# Car_Circuitry.net
KiCad netlist of a schematic drawn in Altium Designer
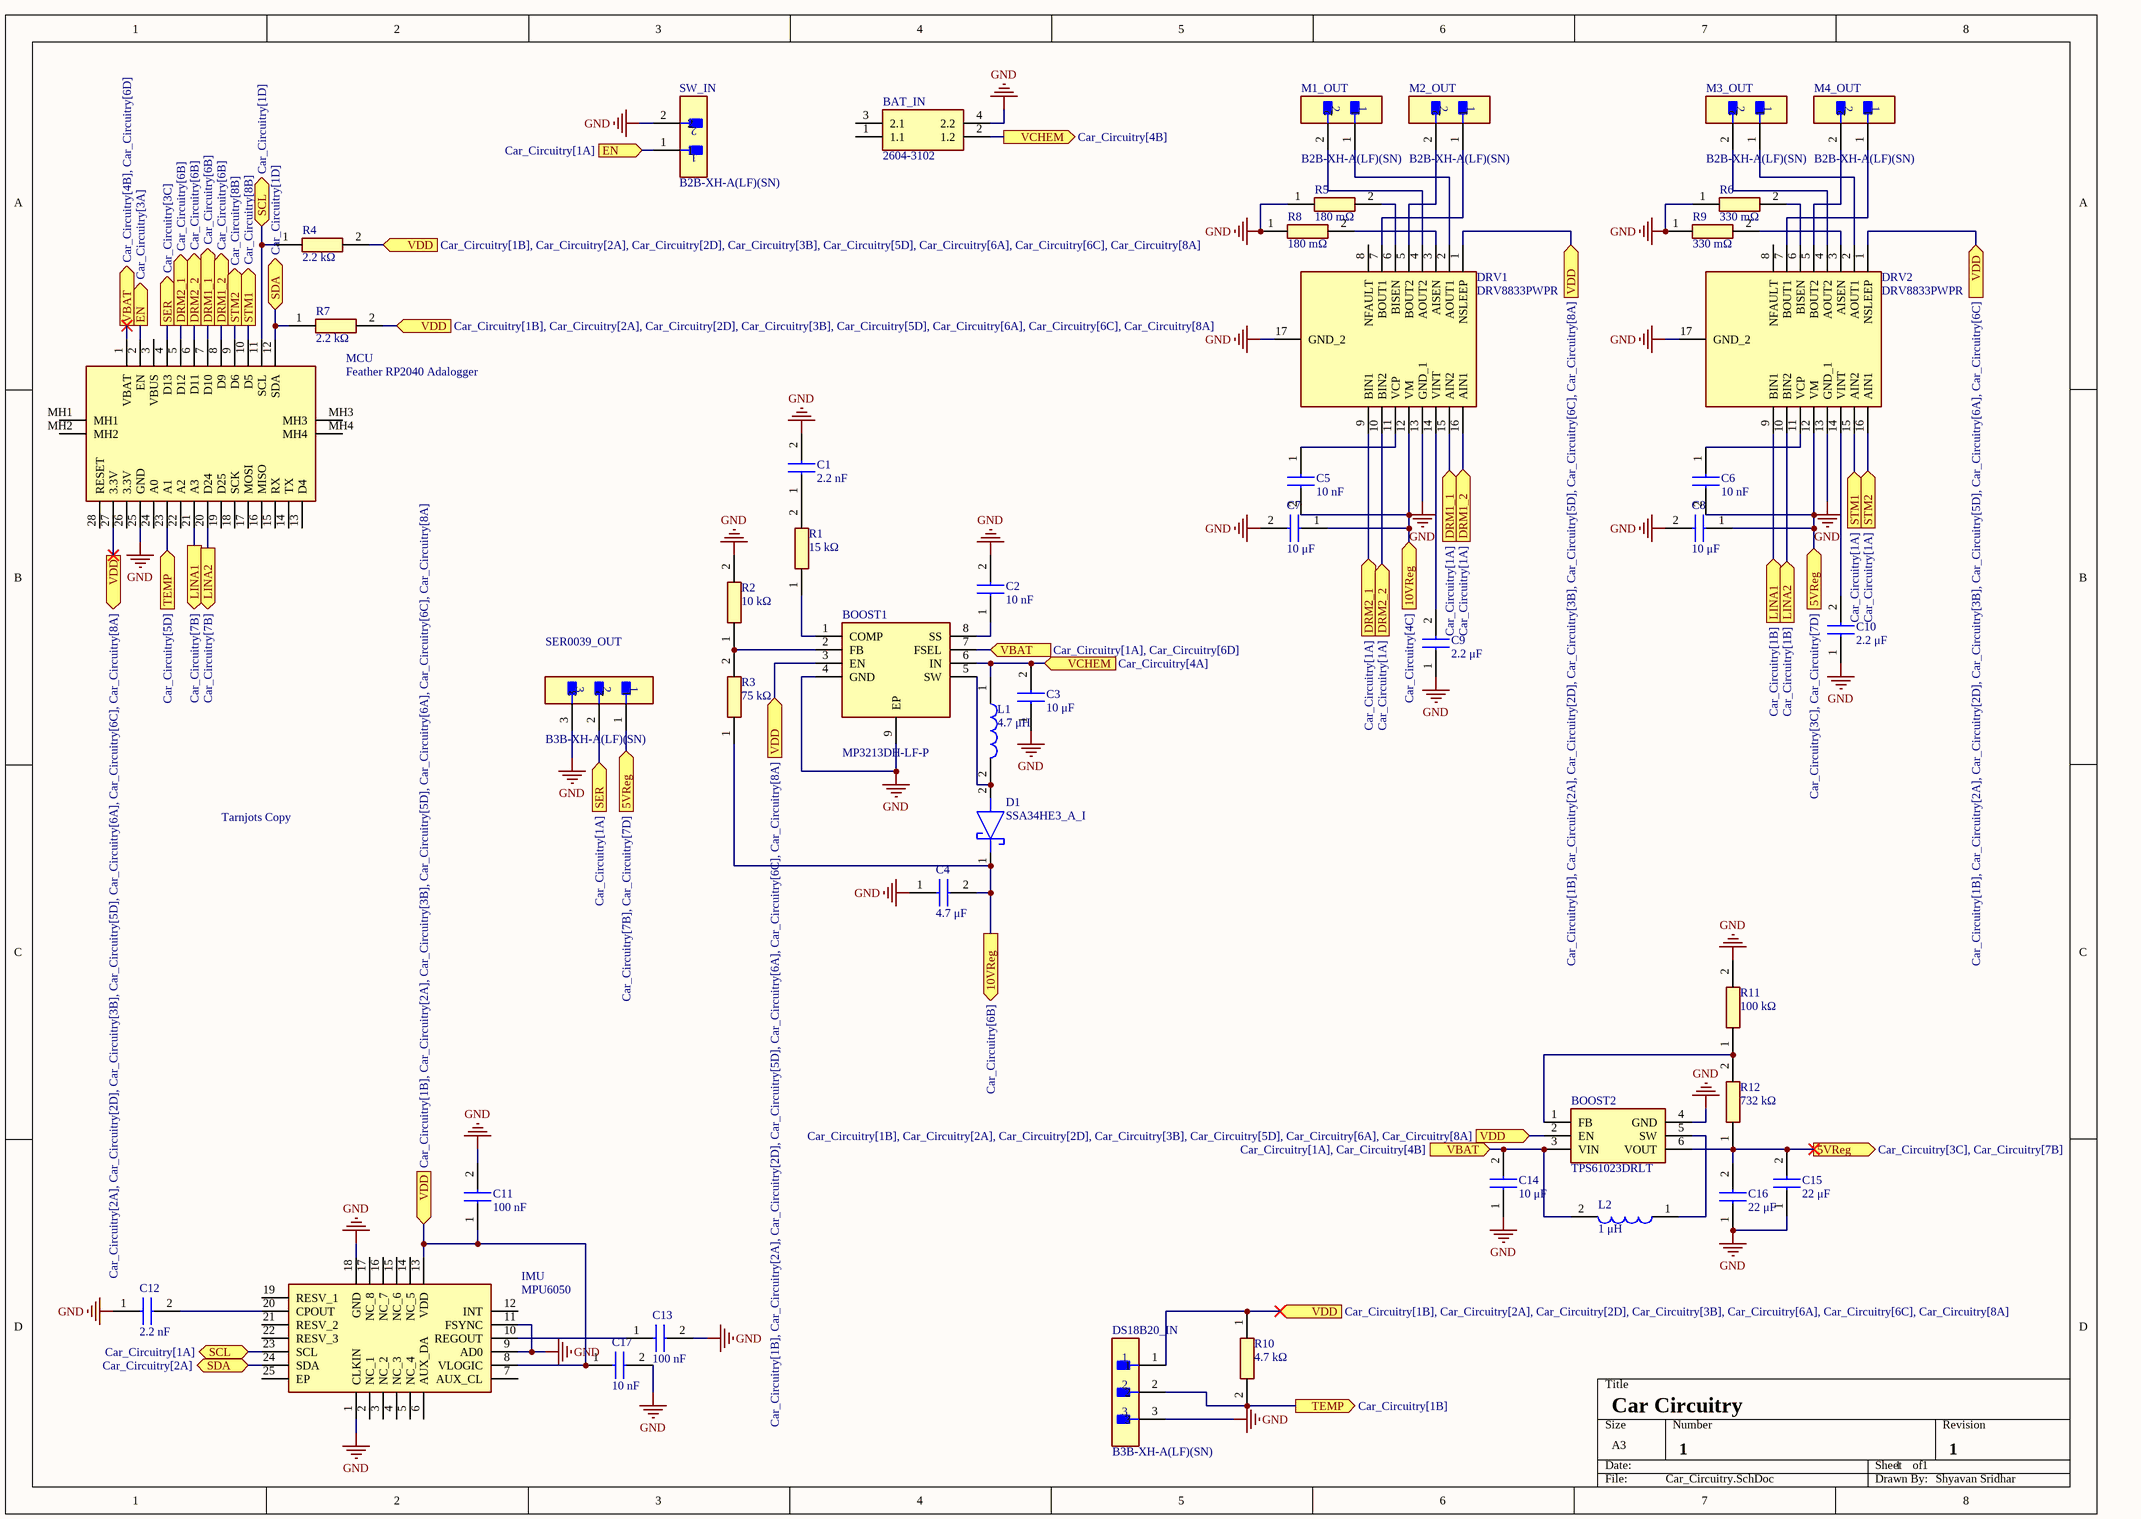
[diagram p0: Car_Circuitry.SchDoc]

(export (version "E")
  (design (tool "Eeschema 10.0.6"))
  (components
    (comp (ref "BAT_IN")
      (value "2604-3102")
      (footprint "SamacSys:26043102")
      (description "Connector")
      (libsource (lib "*") (part "2604-3102"))
    )
    (comp (ref "BOOST1")
      (value "MP3213DH-LF-P")
      (footprint "SamacSys:SOP65P490X110-9N")
      (description "Integrated Circuit")
      (fields (field (name "MOUSER PART NUMBER") "946-MP3213DHLFP"))
      (libsource (lib "*") (part "MP3213DH-LF-P"))
    )
    (comp (ref "BOOST2")
      (value "TPS61023DRLT")
      (footprint "SamacSys:SOTFL50P160X60-6N")
      (description "Integrated Circuit")
      (fields (field (name "MOUSER PART NUMBER") "595-TPS61023DRLT"))
      (libsource (lib "*") (part "TPS61023DRLT"))
    )
    (comp (ref "C1")
      (value "2.2 nF")
      (footprint "SamacSys:CAPC2012X75N")
      (description "Capacitor")
      (fields (field (name "MANUFACTURER_PART_NUMBER") "CL21B222KBANNNC"))
      (libsource (lib "*") (part "CL21B222KBANNNC"))
    )
    (comp (ref "C2")
      (value "10 nF")
      (footprint "SamacSys:CAPC2012X75N")
      (description "Capacitor")
      (fields
        (field (name "MANUFACTURER_PART_NUMBER") "CL21B103KBANNNC")
        (field (name "MOUSER PART NUMBER") "187-CL21B103KBANNNC")
      )
      (libsource (lib "*") (part "CL21B103KBANNNC"))
    )
    (comp (ref "C3")
      (value "10 μF")
      (footprint "SamacSys:CAPC2012X140N")
      (description "Capacitor")
      (fields
        (field (name "MANUFACTURER_PART_NUMBER") "CL21B106KOQNNNE")
        (field (name "MOUSER PART NUMBER") "187-CL21B106KOQNNNE")
      )
      (libsource (lib "*") (part "CL21B106KOQNNNE"))
    )
    (comp (ref "C4")
      (value "4.7 μF")
      (footprint "SamacSys:CAPC2012X135N")
      (description "Capacitor")
      (fields
        (field (name "MANUFACTURER_PART_NUMBER") "CL21B475KOFNNNE")
        (field (name "MOUSER PART NUMBER") "187-CL21B475KOFNNNE")
      )
      (libsource (lib "*") (part "CL21B475KOFNNNE"))
    )
    (comp (ref "C5")
      (value "10 nF")
      (footprint "SamacSys:CAPC2012X75N")
      (description "Capacitor")
      (fields
        (field (name "MANUFACTURER_PART_NUMBER") "CL21B103KBANNNC")
        (field (name "MOUSER PART NUMBER") "187-CL21B103KBANNNC")
      )
      (libsource (lib "*") (part "CL21B103KBANNNC"))
    )
    (comp (ref "C6")
      (value "10 nF")
      (footprint "SamacSys:CAPC2012X75N")
      (description "Capacitor")
      (fields
        (field (name "MANUFACTURER_PART_NUMBER") "CL21B103KBANNNC")
        (field (name "MOUSER PART NUMBER") "187-CL21B103KBANNNC")
      )
      (libsource (lib "*") (part "CL21B103KBANNNC"))
    )
    (comp (ref "C7")
      (value "10 μF")
      (footprint "SamacSys:CAPC2012X140N")
      (description "Capacitor")
      (fields
        (field (name "MANUFACTURER_PART_NUMBER") "CL21B106KOQNNNE")
        (field (name "MOUSER PART NUMBER") "187-CL21B106KOQNNNE")
      )
      (libsource (lib "*") (part "CL21B106KOQNNNE"))
    )
    (comp (ref "C8")
      (value "10 μF")
      (footprint "SamacSys:CAPC2012X140N")
      (description "Capacitor")
      (fields
        (field (name "MANUFACTURER_PART_NUMBER") "CL21B106KOQNNNE")
        (field (name "MOUSER PART NUMBER") "187-CL21B106KOQNNNE")
      )
      (libsource (lib "*") (part "CL21B106KOQNNNE"))
    )
    (comp (ref "C9")
      (value "2.2 μF")
      (footprint "SamacSys:CAPC2012X135N")
      (description "Capacitor")
      (fields (field (name "MANUFACTURER_PART_NUMBER") "CL21B225KAFNNWE"))
      (libsource (lib "*") (part "CL21B225KAFNNWE"))
    )
    (comp (ref "C10")
      (value "2.2 μF")
      (footprint "SamacSys:CAPC2012X135N")
      (description "Capacitor")
      (fields (field (name "MANUFACTURER_PART_NUMBER") "CL21B225KAFNNWE"))
      (libsource (lib "*") (part "CL21B225KAFNNWE"))
    )
    (comp (ref "C11")
      (value "100 nF")
      (footprint "SamacSys:CAPC2012X95N")
      (description "Capacitor")
      (fields
        (field (name "MANUFACTURER_PART_NUMBER") "CL21B104KBCNNNC")
        (field (name "MOUSER PART NUMBER") "187-CL21B104KBCNNNC")
      )
      (libsource (lib "*") (part "CL21B104KBCNNNC"))
    )
    (comp (ref "C12")
      (value "2.2 nF")
      (footprint "SamacSys:CAPC2012X75N")
      (description "Capacitor")
      (fields (field (name "MANUFACTURER_PART_NUMBER") "CL21B222KBANNNC"))
      (libsource (lib "*") (part "CL21B222KBANNNC"))
    )
    (comp (ref "C13")
      (value "100 nF")
      (footprint "SamacSys:CAPC2012X95N")
      (description "Capacitor")
      (fields
        (field (name "MANUFACTURER_PART_NUMBER") "CL21B104KBCNNNC")
        (field (name "MOUSER PART NUMBER") "187-CL21B104KBCNNNC")
      )
      (libsource (lib "*") (part "CL21B104KBCNNNC"))
    )
    (comp (ref "C14")
      (value "10 μF")
      (footprint "SamacSys:CAPC2012X140N")
      (description "Capacitor")
      (fields
        (field (name "MANUFACTURER_PART_NUMBER") "CL21B106KOQNNNE")
        (field (name "MOUSER PART NUMBER") "187-CL21B106KOQNNNE")
      )
      (libsource (lib "*") (part "CL21B106KOQNNNE"))
    )
    (comp (ref "C15")
      (value "22 μF")
      (footprint "SamacSys:CAPC3216X180N")
      (description "Capacitor")
      (fields
        (field (name "MANUFACTURER_PART_NUMBER") "CL31B226KPHNNNE")
        (field (name "MOUSER PART NUMBER") "187-CL31B226KPHNNNE")
      )
      (libsource (lib "*") (part "CL31B226KPHNNNE"))
    )
    (comp (ref "C16")
      (value "22 μF")
      (footprint "SamacSys:CAPC3216X180N")
      (description "Capacitor")
      (fields
        (field (name "MANUFACTURER_PART_NUMBER") "CL31B226KPHNNNE")
        (field (name "MOUSER PART NUMBER") "187-CL31B226KPHNNNE")
      )
      (libsource (lib "*") (part "CL31B226KPHNNNE"))
    )
    (comp (ref "C17")
      (value "10 nF")
      (footprint "SamacSys:CAPC2012X75N")
      (description "Capacitor")
      (fields
        (field (name "MANUFACTURER_PART_NUMBER") "CL21B103KBANNNC")
        (field (name "MOUSER PART NUMBER") "187-CL21B103KBANNNC")
      )
      (libsource (lib "*") (part "CL21B103KBANNNC"))
    )
    (comp (ref "D1")
      (value "SSA34HE3_A_I")
      (footprint "SamacSys:DIONM5127X229N")
      (description "Schottky Diode")
      (fields
        (field (name "MANUFACTURER_PART_NUMBER") "SSA34HE3_A/I")
        (field (name "MOUSER PART NUMBER") "78-SSA34HE3_A/I")
      )
      (libsource (lib "*") (part "SSA34HE3_A_I"))
    )
    (comp (ref "DRV1")
      (value "DRV8833PWPR")
      (footprint "SamacSys:SOP65P640X120-17N")
      (description "Integrated Circuit")
      (fields
        (field (name "MANUFACTURER_PART_NUMBER") "DRV8833PWP")
        (field (name "MOUSER PART NUMBER") "595-DRV8833PWP")
      )
      (libsource (lib "*") (part "DRV8833PWP"))
    )
    (comp (ref "DRV2")
      (value "DRV8833PWPR")
      (footprint "SamacSys:SOP65P640X120-17N")
      (description "Integrated Circuit")
      (fields
        (field (name "MANUFACTURER_PART_NUMBER") "DRV8833PWP")
        (field (name "MOUSER PART NUMBER") "595-DRV8833PWP")
      )
      (libsource (lib "*") (part "DRV8833PWP"))
    )
    (comp (ref "DS18B20_IN")
      (value "B3B-XH-A(LF)(SN)")
      (footprint "FP-B3B-XH-A_LF_SN-MFG")
      (description "CONN HEADER VERT 3POS 2.5MM")
      (libsource (lib "") (part "0d3f023dd272f625e17a2be33dea85f_1"))
    )
    (comp (ref "IMU")
      (value "MPU6050")
      (footprint "SamacSys:MPU6050")
      (description "IMU")
      (libsource (lib "*") (part "MPU6050"))
    )
    (comp (ref "L1")
      (value "4.7 μH")
      (footprint "SamacSys:CDRH8D43NP4R7NC")
      (description "Inductor")
      (fields
        (field (name "MANUFACTURER_PART_NUMBER") "CDRH8D43NP-4R7NC")
        (field (name "MOUSER PART NUMBER") "851-CDRH8D43NP-4R7NC")
      )
      (libsource (lib "*") (part "CDRH8D43NP-4R7NC"))
    )
    (comp (ref "L2")
      (value "1 μH")
      (footprint "SamacSys:74438357010")
      (description "Inductor")
      (fields
        (field (name "MANUFACTURER_PART_NUMBER") "74438357010")
        (field (name "MOUSER PART NUMBER") "710-74438357010")
      )
      (libsource (lib "*") (part "74438357010"))
    )
    (comp (ref "M1_OUT")
      (value "B2B-XH-A(LF)(SN)")
      (footprint "FP-B2B-XH-A_LF_SN-MFG")
      (description "CONN HEADER VERT 2POS 2.5MM")
      (libsource (lib "Altium Content Vault") (part "3bc925449376181038e59eaffc5286c"))
    )
    (comp (ref "M2_OUT")
      (value "B2B-XH-A(LF)(SN)")
      (footprint "FP-B2B-XH-A_LF_SN-MFG")
      (description "CONN HEADER VERT 2POS 2.5MM")
      (libsource (lib "Altium Content Vault") (part "3bc925449376181038e59eaffc5286c"))
    )
    (comp (ref "M3_OUT")
      (value "B2B-XH-A(LF)(SN)")
      (footprint "FP-B2B-XH-A_LF_SN-MFG")
      (description "CONN HEADER VERT 2POS 2.5MM")
      (libsource (lib "Altium Content Vault") (part "3bc925449376181038e59eaffc5286c"))
    )
    (comp (ref "M4_OUT")
      (value "B2B-XH-A(LF)(SN)")
      (footprint "FP-B2B-XH-A_LF_SN-MFG")
      (description "CONN HEADER VERT 2POS 2.5MM")
      (libsource (lib "Altium Content Vault") (part "3bc925449376181038e59eaffc5286c"))
    )
    (comp (ref "MCU")
      (value "Feather RP2040 Adalogger")
      (footprint "SamacSys:2796")
      (description "Adafruit Microcontroller")
      (fields (field (name "MANUFACTURER_PART_NUMBER") "2796") (field (name "MOUSER PART NUMBER") "485-2796"))
      (libsource (lib "*") (part "2796"))
    )
    (comp (ref "R1")
      (value "15 kΩ")
      (footprint "SamacSys:RESC3216X70N")
      (description "Resistor")
      (fields (field (name "MANUFACTURER_PART_NUMBER") "RMCF1206FT15K0"))
      (libsource (lib "*") (part "RMCF1206FT15K0"))
    )
    (comp (ref "R2")
      (value "10 kΩ")
      (footprint "SamacSys:RESC3216X70N")
      (description "Resistor")
      (fields
        (field (name "MANUFACTURER_PART_NUMBER") "RMCF1206FT10K0")
        (field (name "MOUSER PART NUMBER") "708-RMCF1206FT10K0")
      )
      (libsource (lib "*") (part "RMCF1206FT10K0"))
    )
    (comp (ref "R3")
      (value "75 kΩ")
      (footprint "SamacSys:RESC3116X65N")
      (description "Resistor")
      (fields
        (field (name "MANUFACTURER_PART_NUMBER") "RC1206FR-0775KL")
        (field (name "MOUSER PART NUMBER") "603-RC1206FR-0775KL")
      )
      (libsource (lib "*") (part "RC1206FR-0775KL"))
    )
    (comp (ref "R4")
      (value "2.2 kΩ")
      (footprint "SamacSys:RESAD1042W49L330D178")
      (description "Resistor")
      (fields (field (name "MANUFACTURER_PART_NUMBER") "RNMF14FTC2K20"))
      (libsource (lib "*") (part "RNMF14FTC2K20"))
    )
    (comp (ref "R5")
      (value "180 mΩ")
      (footprint "SamacSys:ERJ6_B_BW_R_LW_CW_D")
      (description "Resistor")
      (fields
        (field (name "MANUFACTURER_PART_NUMBER") "ERJ-6DSFR18V")
        (field (name "MOUSER PART NUMBER") "667-ERJ-6DSFR18V")
      )
      (libsource (lib "*") (part "ERJ-6DSFR18V"))
    )
    (comp (ref "R6")
      (value "330 mΩ")
      (footprint "SamacSys:ERJ6_B_BW_R_LW_CW_D")
      (description "Resistor")
      (fields
        (field (name "MANUFACTURER_PART_NUMBER") "ERJ-6DQFR33V")
        (field (name "MOUSER PART NUMBER") "667-ERJ-6DQFR33V")
      )
      (libsource (lib "*") (part "ERJ-6DQFR33V"))
    )
    (comp (ref "R7")
      (value "2.2 kΩ")
      (footprint "SamacSys:RESAD1042W49L330D178")
      (description "Resistor")
      (fields (field (name "MANUFACTURER_PART_NUMBER") "RNMF14FTC2K20"))
      (libsource (lib "*") (part "RNMF14FTC2K20"))
    )
    (comp (ref "R8")
      (value "180 mΩ")
      (footprint "SamacSys:ERJ6_B_BW_R_LW_CW_D")
      (description "Resistor")
      (fields
        (field (name "MANUFACTURER_PART_NUMBER") "ERJ-6DSFR18V")
        (field (name "MOUSER PART NUMBER") "667-ERJ-6DSFR18V")
      )
      (libsource (lib "*") (part "ERJ-6DSFR18V"))
    )
    (comp (ref "R9")
      (value "330 mΩ")
      (footprint "SamacSys:ERJ6_B_BW_R_LW_CW_D")
      (description "Resistor")
      (fields
        (field (name "MANUFACTURER_PART_NUMBER") "ERJ-6DQFR33V")
        (field (name "MOUSER PART NUMBER") "667-ERJ-6DQFR33V")
      )
      (libsource (lib "*") (part "ERJ-6DQFR33V"))
    )
    (comp (ref "R10")
      (value "4.7 kΩ")
      (footprint "SamacSys:RESAD1530W60L610D230")
      (description "Resistor")
      (fields
        (field (name "MANUFACTURER_PART_NUMBER") "CF1/4C472J")
        (field (name "MOUSER PART NUMBER") "660-CF1/4C472J")
      )
      (libsource (lib "*") (part "CF1_4C472J"))
    )
    (comp (ref "R11")
      (value "100 kΩ")
      (footprint "SamacSys:ERJ8ENF1000V")
      (description "Resistor")
      (fields
        (field (name "MANUFACTURER_PART_NUMBER") "ERJ-8ENF1003V")
        (field (name "MOUSER PART NUMBER") "667-ERJ-8ENF1003V")
      )
      (libsource (lib "*") (part "ERJ-8ENF1003V"))
    )
    (comp (ref "R12")
      (value "732 kΩ")
      (footprint "SamacSys:ERJ8ENF1000V")
      (description "Resistor")
      (fields
        (field (name "MANUFACTURER_PART_NUMBER") "ERJ-8ENF7323V")
        (field (name "MOUSER PART NUMBER") "667-ERJ-8ENF7323V")
      )
      (libsource (lib "*") (part "ERJ-8ENF7323V"))
    )
    (comp (ref "SER0039_OUT")
      (value "B3B-XH-A(LF)(SN)")
      (footprint "FP-B3B-XH-A_LF_SN-MFG")
      (description "CONN HEADER VERT 3POS 2.5MM")
      (libsource (lib "Altium Content Vault") (part "0d3f023dd272f625e17a2be33dea85f"))
    )
    (comp (ref "SW_IN")
      (value "B2B-XH-A(LF)(SN)")
      (footprint "FP-B2B-XH-A_LF_SN-MFG")
      (description "CONN HEADER VERT 2POS 2.5MM")
      (libsource (lib "") (part "3bc925449376181038e59eaffc5286c_1"))
    )
  )
  (nets
    (net (code "1") (name "/5VReg") (class "Default")
      (node (ref "BOOST2") (pin "6") (pinfunction "VOUT_6") (pintype "passive"))
      (node (ref "C15") (pin "2") (pinfunction "2_2") (pintype "passive"))
      (node (ref "C16") (pin "2") (pinfunction "2_2") (pintype "passive"))
      (node (ref "C6") (pin "2") (pinfunction "2_2") (pintype "passive"))
      (node (ref "C8") (pin "1") (pinfunction "1_1") (pintype "passive"))
      (node (ref "DRV2") (pin "12") (pinfunction "VM_12") (pintype "passive"))
      (node (ref "R12") (pin "1") (pinfunction "1_1") (pintype "passive"))
      (node (ref "SER0039_OUT") (pin "1") (pinfunction "1_1") (pintype "passive"))
    )
    (net (code "2") (name "/10VReg") (class "Default")
      (node (ref "C4") (pin "2") (pinfunction "2_2") (pintype "passive"))
      (node (ref "C5") (pin "2") (pinfunction "2_2") (pintype "passive"))
      (node (ref "C7") (pin "1") (pinfunction "1_1") (pintype "passive"))
      (node (ref "D1") (pin "1") (pinfunction "K_1") (pintype "passive"))
      (node (ref "DRV1") (pin "12") (pinfunction "VM_12") (pintype "passive"))
      (node (ref "R3") (pin "1") (pinfunction "1_1") (pintype "passive"))
    )
    (net (code "3") (name "/DRM1_1") (class "Default")
      (node (ref "DRV1") (pin "15") (pinfunction "AIN2_15") (pintype "passive"))
      (node (ref "MCU") (pin "7") (pinfunction "D10_7") (pintype "passive"))
    )
    (net (code "4") (name "/DRM1_2") (class "Default")
      (node (ref "DRV1") (pin "16") (pinfunction "AIN1_16") (pintype "passive"))
      (node (ref "MCU") (pin "8") (pinfunction "D9_8") (pintype "passive"))
    )
    (net (code "5") (name "/DRM2_1") (class "Default")
      (node (ref "DRV1") (pin "9") (pinfunction "BIN1_9") (pintype "passive"))
      (node (ref "MCU") (pin "5") (pinfunction "D12_5") (pintype "passive"))
    )
    (net (code "6") (name "/DRM2_2") (class "Default")
      (node (ref "DRV1") (pin "10") (pinfunction "BIN2_10") (pintype "passive"))
      (node (ref "MCU") (pin "6") (pinfunction "D11_6") (pintype "passive"))
    )
    (net (code "7") (name "/EN") (class "Default")
      (node (ref "MCU") (pin "2") (pinfunction "EN_2") (pintype "passive"))
      (node (ref "SW_IN") (pin "1") (pinfunction "1_1") (pintype "passive"))
    )
    (net (code "8") (name "/LINA1") (class "Default")
      (node (ref "DRV2") (pin "9") (pinfunction "BIN1_9") (pintype "passive"))
      (node (ref "MCU") (pin "21") (pinfunction "A3_21") (pintype "passive"))
    )
    (net (code "9") (name "/LINA2") (class "Default")
      (node (ref "DRV2") (pin "10") (pinfunction "BIN2_10") (pintype "passive"))
      (node (ref "MCU") (pin "20") (pinfunction "D24_20") (pintype "passive"))
    )
    (net (code "10") (name "/SCL") (class "Default")
      (node (ref "IMU") (pin "23") (pinfunction "SCL_23") (pintype "passive"))
      (node (ref "MCU") (pin "11") (pinfunction "SCL_11") (pintype "passive"))
      (node (ref "R4") (pin "1") (pinfunction "1_1") (pintype "passive"))
    )
    (net (code "11") (name "/SDA") (class "Default")
      (node (ref "IMU") (pin "24") (pinfunction "SDA_24") (pintype "passive"))
      (node (ref "MCU") (pin "12") (pinfunction "SDA_12") (pintype "passive"))
      (node (ref "R7") (pin "1") (pinfunction "1_1") (pintype "passive"))
    )
    (net (code "12") (name "/SER") (class "Default")
      (node (ref "MCU") (pin "4") (pinfunction "D13_4") (pintype "passive"))
      (node (ref "SER0039_OUT") (pin "2") (pinfunction "2_2") (pintype "passive"))
    )
    (net (code "13") (name "/STM1") (class "Default")
      (node (ref "DRV2") (pin "15") (pinfunction "AIN2_15") (pintype "passive"))
      (node (ref "MCU") (pin "10") (pinfunction "D5_10") (pintype "passive"))
    )
    (net (code "14") (name "/STM2") (class "Default")
      (node (ref "DRV2") (pin "16") (pinfunction "AIN1_16") (pintype "passive"))
      (node (ref "MCU") (pin "9") (pinfunction "D6_9") (pintype "passive"))
    )
    (net (code "15") (name "/TEMP") (class "Default")
      (node (ref "DS18B20_IN") (pin "2") (pinfunction "2_2") (pintype "passive"))
      (node (ref "MCU") (pin "23") (pinfunction "A1_23") (pintype "passive"))
      (node (ref "R10") (pin "2") (pinfunction "2_2") (pintype "passive"))
    )
    (net (code "16") (name "/VBAT") (class "Default")
      (node (ref "BOOST1") (pin "7") (pinfunction "FSEL_7") (pintype "passive"))
      (node (ref "BOOST2") (pin "3") (pinfunction "VIN_3") (pintype "passive"))
      (node (ref "C14") (pin "2") (pinfunction "2_2") (pintype "passive"))
      (node (ref "L2") (pin "2") (pinfunction "2_2") (pintype "passive"))
      (node (ref "MCU") (pin "1") (pinfunction "VBAT_1") (pintype "passive"))
    )
    (net (code "17") (name "/VCHEM") (class "Default")
      (node (ref "BAT_IN") (pin "2") (pinfunction "1.2_2") (pintype "passive"))
      (node (ref "BOOST1") (pin "6") (pinfunction "IN_6") (pintype "passive"))
      (node (ref "C3") (pin "2") (pinfunction "2_2") (pintype "passive"))
      (node (ref "L1") (pin "1") (pinfunction "1_1") (pintype "passive"))
    )
    (net (code "18") (name "/VDD") (class "Default")
      (node (ref "BOOST1") (pin "3") (pinfunction "EN_3") (pintype "passive"))
      (node (ref "BOOST2") (pin "2") (pinfunction "EN_2") (pintype "passive"))
      (node (ref "C11") (pin "1") (pinfunction "1_1") (pintype "passive"))
      (node (ref "C17") (pin "1") (pinfunction "1_1") (pintype "passive"))
      (node (ref "DRV1") (pin "1") (pinfunction "NSLEEP_1") (pintype "passive"))
      (node (ref "DRV2") (pin "1") (pinfunction "NSLEEP_1") (pintype "passive"))
      (node (ref "DS18B20_IN") (pin "1") (pinfunction "1_1") (pintype "passive"))
      (node (ref "IMU") (pin "13") (pinfunction "VDD_13") (pintype "passive"))
      (node (ref "IMU") (pin "8") (pinfunction "VLOGIC_8") (pintype "passive"))
      (node (ref "MCU") (pin "27") (pinfunction "3.3V_27") (pintype "passive"))
      (node (ref "R10") (pin "1") (pinfunction "1_1") (pintype "passive"))
      (node (ref "R4") (pin "2") (pinfunction "2_2") (pintype "passive"))
      (node (ref "R7") (pin "2") (pinfunction "2_2") (pintype "passive"))
    )
    (net (code "19") (name "GND") (class "Default")
      (node (ref "BAT_IN") (pin "4") (pinfunction "2.2_4") (pintype "passive"))
      (node (ref "BOOST1") (pin "4") (pinfunction "GND_4") (pintype "passive"))
      (node (ref "BOOST1") (pin "9") (pinfunction "EP_9") (pintype "passive"))
      (node (ref "BOOST2") (pin "4") (pinfunction "GND_4") (pintype "passive"))
      (node (ref "C1") (pin "2") (pinfunction "2_2") (pintype "passive"))
      (node (ref "C10") (pin "1") (pinfunction "1_1") (pintype "passive"))
      (node (ref "C11") (pin "2") (pinfunction "2_2") (pintype "passive"))
      (node (ref "C12") (pin "1") (pinfunction "1_1") (pintype "passive"))
      (node (ref "C13") (pin "2") (pinfunction "2_2") (pintype "passive"))
      (node (ref "C14") (pin "1") (pinfunction "1_1") (pintype "passive"))
      (node (ref "C15") (pin "1") (pinfunction "1_1") (pintype "passive"))
      (node (ref "C16") (pin "1") (pinfunction "1_1") (pintype "passive"))
      (node (ref "C17") (pin "2") (pinfunction "2_2") (pintype "passive"))
      (node (ref "C2") (pin "2") (pinfunction "2_2") (pintype "passive"))
      (node (ref "C3") (pin "1") (pinfunction "1_1") (pintype "passive"))
      (node (ref "C4") (pin "1") (pinfunction "1_1") (pintype "passive"))
      (node (ref "C7") (pin "2") (pinfunction "2_2") (pintype "passive"))
      (node (ref "C8") (pin "2") (pinfunction "2_2") (pintype "passive"))
      (node (ref "C9") (pin "1") (pinfunction "1_1") (pintype "passive"))
      (node (ref "DRV1") (pin "13") (pinfunction "GND_1_13") (pintype "passive"))
      (node (ref "DRV1") (pin "17") (pinfunction "GND_2_17") (pintype "passive"))
      (node (ref "DRV2") (pin "13") (pinfunction "GND_1_13") (pintype "passive"))
      (node (ref "DRV2") (pin "17") (pinfunction "GND_2_17") (pintype "passive"))
      (node (ref "DS18B20_IN") (pin "3") (pinfunction "3_3") (pintype "passive"))
      (node (ref "IMU") (pin "1") (pinfunction "CLKIN_1") (pintype "passive"))
      (node (ref "IMU") (pin "11") (pinfunction "FSYNC_11") (pintype "passive"))
      (node (ref "IMU") (pin "18") (pinfunction "GND_18") (pintype "passive"))
      (node (ref "IMU") (pin "9") (pinfunction "AD0_9") (pintype "passive"))
      (node (ref "MCU") (pin "25") (pinfunction "GND_25") (pintype "passive"))
      (node (ref "R11") (pin "2") (pinfunction "2_2") (pintype "passive"))
      (node (ref "R2") (pin "2") (pinfunction "2_2") (pintype "passive"))
      (node (ref "R5") (pin "1") (pinfunction "1_1") (pintype "passive"))
      (node (ref "R6") (pin "1") (pinfunction "1_1") (pintype "passive"))
      (node (ref "R8") (pin "1") (pinfunction "1_1") (pintype "passive"))
      (node (ref "R9") (pin "1") (pinfunction "1_1") (pintype "passive"))
      (node (ref "SER0039_OUT") (pin "3") (pinfunction "3_3") (pintype "passive"))
      (node (ref "SW_IN") (pin "2") (pinfunction "2_2") (pintype "passive"))
    )
    (net (code "20") (name "Net-(BOOST1-COMP)") (class "Default")
      (node (ref "BOOST1") (pin "1") (pinfunction "COMP_1") (pintype "passive"))
      (node (ref "R1") (pin "1") (pinfunction "1_1") (pintype "passive"))
    )
    (net (code "21") (name "Net-(BOOST1-FB)") (class "Default")
      (node (ref "BOOST1") (pin "2") (pinfunction "FB_2") (pintype "passive"))
      (node (ref "R2") (pin "1") (pinfunction "1_1") (pintype "passive"))
      (node (ref "R3") (pin "2") (pinfunction "2_2") (pintype "passive"))
    )
    (net (code "22") (name "Net-(BOOST1-SS)") (class "Default")
      (node (ref "BOOST1") (pin "8") (pinfunction "SS_8") (pintype "passive"))
      (node (ref "C2") (pin "1") (pinfunction "1_1") (pintype "passive"))
    )
    (net (code "23") (name "Net-(BOOST1-SW)") (class "Default")
      (node (ref "BOOST1") (pin "5") (pinfunction "SW_5") (pintype "passive"))
      (node (ref "D1") (pin "2") (pinfunction "A_2") (pintype "passive"))
      (node (ref "L1") (pin "2") (pinfunction "2_2") (pintype "passive"))
    )
    (net (code "24") (name "Net-(BOOST2-FB)") (class "Default")
      (node (ref "BOOST2") (pin "1") (pinfunction "FB_1") (pintype "passive"))
      (node (ref "R11") (pin "1") (pinfunction "1_1") (pintype "passive"))
      (node (ref "R12") (pin "2") (pinfunction "2_2") (pintype "passive"))
    )
    (net (code "25") (name "Net-(BOOST2-SW)") (class "Default")
      (node (ref "BOOST2") (pin "5") (pinfunction "SW_5") (pintype "passive"))
      (node (ref "L2") (pin "1") (pinfunction "1_1") (pintype "passive"))
    )
    (net (code "26") (name "Net-(C1-Pad1)") (class "Default")
      (node (ref "C1") (pin "1") (pinfunction "1_1") (pintype "passive"))
      (node (ref "R1") (pin "2") (pinfunction "2_2") (pintype "passive"))
    )
    (net (code "27") (name "Net-(DRV1-AISEN)") (class "Default")
      (node (ref "DRV1") (pin "3") (pinfunction "AISEN_3") (pintype "passive"))
      (node (ref "R8") (pin "2") (pinfunction "2_2") (pintype "passive"))
    )
    (net (code "28") (name "Net-(DRV1-AOUT1)") (class "Default")
      (node (ref "DRV1") (pin "2") (pinfunction "AOUT1_2") (pintype "passive"))
      (node (ref "M1_OUT") (pin "1") (pinfunction "1_1") (pintype "passive"))
    )
    (net (code "29") (name "Net-(DRV1-AOUT2)") (class "Default")
      (node (ref "DRV1") (pin "4") (pinfunction "AOUT2_4") (pintype "passive"))
      (node (ref "M1_OUT") (pin "2") (pinfunction "2_2") (pintype "passive"))
    )
    (net (code "30") (name "Net-(DRV1-BISEN)") (class "Default")
      (node (ref "DRV1") (pin "6") (pinfunction "BISEN_6") (pintype "passive"))
      (node (ref "R5") (pin "2") (pinfunction "2_2") (pintype "passive"))
    )
    (net (code "31") (name "Net-(DRV1-BOUT1)") (class "Default")
      (node (ref "DRV1") (pin "7") (pinfunction "BOUT1_7") (pintype "passive"))
      (node (ref "M2_OUT") (pin "1") (pinfunction "1_1") (pintype "passive"))
    )
    (net (code "32") (name "Net-(DRV1-BOUT2)") (class "Default")
      (node (ref "DRV1") (pin "5") (pinfunction "BOUT2_5") (pintype "passive"))
      (node (ref "M2_OUT") (pin "2") (pinfunction "2_2") (pintype "passive"))
    )
    (net (code "33") (name "Net-(DRV1-VCP)") (class "Default")
      (node (ref "C5") (pin "1") (pinfunction "1_1") (pintype "passive"))
      (node (ref "DRV1") (pin "11") (pinfunction "VCP_11") (pintype "passive"))
    )
    (net (code "34") (name "Net-(DRV1-VINT)") (class "Default")
      (node (ref "C9") (pin "2") (pinfunction "2_2") (pintype "passive"))
      (node (ref "DRV1") (pin "14") (pinfunction "VINT_14") (pintype "passive"))
    )
    (net (code "35") (name "Net-(DRV2-AISEN)") (class "Default")
      (node (ref "DRV2") (pin "3") (pinfunction "AISEN_3") (pintype "passive"))
      (node (ref "R9") (pin "2") (pinfunction "2_2") (pintype "passive"))
    )
    (net (code "36") (name "Net-(DRV2-AOUT1)") (class "Default")
      (node (ref "DRV2") (pin "2") (pinfunction "AOUT1_2") (pintype "passive"))
      (node (ref "M3_OUT") (pin "1") (pinfunction "1_1") (pintype "passive"))
    )
    (net (code "37") (name "Net-(DRV2-AOUT2)") (class "Default")
      (node (ref "DRV2") (pin "4") (pinfunction "AOUT2_4") (pintype "passive"))
      (node (ref "M3_OUT") (pin "2") (pinfunction "2_2") (pintype "passive"))
    )
    (net (code "38") (name "Net-(DRV2-BISEN)") (class "Default")
      (node (ref "DRV2") (pin "6") (pinfunction "BISEN_6") (pintype "passive"))
      (node (ref "R6") (pin "2") (pinfunction "2_2") (pintype "passive"))
    )
    (net (code "39") (name "Net-(DRV2-BOUT1)") (class "Default")
      (node (ref "DRV2") (pin "7") (pinfunction "BOUT1_7") (pintype "passive"))
      (node (ref "M4_OUT") (pin "1") (pinfunction "1_1") (pintype "passive"))
    )
    (net (code "40") (name "Net-(DRV2-BOUT2)") (class "Default")
      (node (ref "DRV2") (pin "5") (pinfunction "BOUT2_5") (pintype "passive"))
      (node (ref "M4_OUT") (pin "2") (pinfunction "2_2") (pintype "passive"))
    )
    (net (code "41") (name "Net-(DRV2-VCP)") (class "Default")
      (node (ref "C6") (pin "1") (pinfunction "1_1") (pintype "passive"))
      (node (ref "DRV2") (pin "11") (pinfunction "VCP_11") (pintype "passive"))
    )
    (net (code "42") (name "Net-(DRV2-VINT)") (class "Default")
      (node (ref "C10") (pin "2") (pinfunction "2_2") (pintype "passive"))
      (node (ref "DRV2") (pin "14") (pinfunction "VINT_14") (pintype "passive"))
    )
    (net (code "43") (name "Net-(IMU-CPOUT)") (class "Default")
      (node (ref "C12") (pin "2") (pinfunction "2_2") (pintype "passive"))
      (node (ref "IMU") (pin "20") (pinfunction "CPOUT_20") (pintype "passive"))
    )
    (net (code "44") (name "Net-(IMU-REGOUT)") (class "Default")
      (node (ref "C13") (pin "1") (pinfunction "1_1") (pintype "passive"))
      (node (ref "IMU") (pin "10") (pinfunction "REGOUT_10") (pintype "passive"))
    )
    (net (code "45") (name "unconnected-(BAT_IN-1.1-Pad1)") (class "Default")
      (node (ref "BAT_IN") (pin "1") (pinfunction "1.1_1") (pintype "passive"))
    )
    (net (code "46") (name "unconnected-(BAT_IN-2.1-Pad3)") (class "Default")
      (node (ref "BAT_IN") (pin "3") (pinfunction "2.1_3") (pintype "passive"))
    )
    (net (code "47") (name "unconnected-(DRV1-NFAULT-Pad8)") (class "Default")
      (node (ref "DRV1") (pin "8") (pinfunction "NFAULT_8") (pintype "passive"))
    )
    (net (code "48") (name "unconnected-(DRV2-NFAULT-Pad8)") (class "Default")
      (node (ref "DRV2") (pin "8") (pinfunction "NFAULT_8") (pintype "passive"))
    )
    (net (code "49") (name "unconnected-(IMU-AUX_CL-Pad7)") (class "Default")
      (node (ref "IMU") (pin "7") (pinfunction "AUX_CL_7") (pintype "passive"))
    )
    (net (code "50") (name "unconnected-(IMU-AUX_DA-Pad6)") (class "Default")
      (node (ref "IMU") (pin "6") (pinfunction "AUX_DA_6") (pintype "passive"))
    )
    (net (code "51") (name "unconnected-(IMU-EP-Pad25)") (class "Default")
      (node (ref "IMU") (pin "25") (pinfunction "EP_25") (pintype "passive"))
    )
    (net (code "52") (name "unconnected-(IMU-INT-Pad12)") (class "Default")
      (node (ref "IMU") (pin "12") (pinfunction "INT_12") (pintype "passive"))
    )
    (net (code "53") (name "unconnected-(IMU-NC_1-Pad2)") (class "Default")
      (node (ref "IMU") (pin "2") (pinfunction "NC_1_2") (pintype "passive"))
    )
    (net (code "54") (name "unconnected-(IMU-NC_2-Pad3)") (class "Default")
      (node (ref "IMU") (pin "3") (pinfunction "NC_2_3") (pintype "passive"))
    )
    (net (code "55") (name "unconnected-(IMU-NC_3-Pad4)") (class "Default")
      (node (ref "IMU") (pin "4") (pinfunction "NC_3_4") (pintype "passive"))
    )
    (net (code "56") (name "unconnected-(IMU-NC_4-Pad5)") (class "Default")
      (node (ref "IMU") (pin "5") (pinfunction "NC_4_5") (pintype "passive"))
    )
    (net (code "57") (name "unconnected-(IMU-NC_5-Pad14)") (class "Default")
      (node (ref "IMU") (pin "14") (pinfunction "NC_5_14") (pintype "passive"))
    )
    (net (code "58") (name "unconnected-(IMU-NC_6-Pad15)") (class "Default")
      (node (ref "IMU") (pin "15") (pinfunction "NC_6_15") (pintype "passive"))
    )
    (net (code "59") (name "unconnected-(IMU-NC_7-Pad16)") (class "Default")
      (node (ref "IMU") (pin "16") (pinfunction "NC_7_16") (pintype "passive"))
    )
    (net (code "60") (name "unconnected-(IMU-NC_8-Pad17)") (class "Default")
      (node (ref "IMU") (pin "17") (pinfunction "NC_8_17") (pintype "passive"))
    )
    (net (code "61") (name "unconnected-(IMU-RESV_1-Pad19)") (class "Default")
      (node (ref "IMU") (pin "19") (pinfunction "RESV_1_19") (pintype "passive"))
    )
    (net (code "62") (name "unconnected-(IMU-RESV_2-Pad21)") (class "Default")
      (node (ref "IMU") (pin "21") (pinfunction "RESV_2_21") (pintype "passive"))
    )
    (net (code "63") (name "unconnected-(IMU-RESV_3-Pad22)") (class "Default")
      (node (ref "IMU") (pin "22") (pinfunction "RESV_3_22") (pintype "passive"))
    )
    (net (code "64") (name "unconnected-(MCU-3.3V-Pad26)") (class "Default")
      (node (ref "MCU") (pin "26") (pinfunction "3.3V_26") (pintype "passive"))
    )
    (net (code "65") (name "unconnected-(MCU-A0-Pad24)") (class "Default")
      (node (ref "MCU") (pin "24") (pinfunction "A0_24") (pintype "passive"))
    )
    (net (code "66") (name "unconnected-(MCU-A2-Pad22)") (class "Default")
      (node (ref "MCU") (pin "22") (pinfunction "A2_22") (pintype "passive"))
    )
    (net (code "67") (name "unconnected-(MCU-D4-Pad13)") (class "Default")
      (node (ref "MCU") (pin "13") (pinfunction "D4_13") (pintype "passive"))
    )
    (net (code "68") (name "unconnected-(MCU-D25-Pad19)") (class "Default")
      (node (ref "MCU") (pin "19") (pinfunction "D25_19") (pintype "passive"))
    )
    (net (code "69") (name "unconnected-(MCU-MISO-Pad16)") (class "Default")
      (node (ref "MCU") (pin "16") (pinfunction "MISO_16") (pintype "passive"))
    )
    (net (code "70") (name "unconnected-(MCU-MOSI-Pad17)") (class "Default")
      (node (ref "MCU") (pin "17") (pinfunction "MOSI_17") (pintype "passive"))
    )
    (net (code "71") (name "unconnected-(MCU-PadMH1)") (class "Default")
      (node (ref "MCU") (pin "MH1") (pinfunction "MH1_MH1") (pintype "passive"))
    )
    (net (code "72") (name "unconnected-(MCU-PadMH2)") (class "Default")
      (node (ref "MCU") (pin "MH2") (pinfunction "MH2_MH2") (pintype "passive"))
    )
    (net (code "73") (name "unconnected-(MCU-PadMH3)") (class "Default")
      (node (ref "MCU") (pin "MH3") (pinfunction "MH3_MH3") (pintype "passive"))
    )
    (net (code "74") (name "unconnected-(MCU-PadMH4)") (class "Default")
      (node (ref "MCU") (pin "MH4") (pinfunction "MH4_MH4") (pintype "passive"))
    )
    (net (code "75") (name "unconnected-(MCU-RESET-Pad28)") (class "Default")
      (node (ref "MCU") (pin "28") (pinfunction "RESET_28") (pintype "passive"))
    )
    (net (code "76") (name "unconnected-(MCU-RX-Pad15)") (class "Default")
      (node (ref "MCU") (pin "15") (pinfunction "RX_15") (pintype "passive"))
    )
    (net (code "77") (name "unconnected-(MCU-SCK-Pad18)") (class "Default")
      (node (ref "MCU") (pin "18") (pinfunction "SCK_18") (pintype "passive"))
    )
    (net (code "78") (name "unconnected-(MCU-TX-Pad14)") (class "Default")
      (node (ref "MCU") (pin "14") (pinfunction "TX_14") (pintype "passive"))
    )
    (net (code "79") (name "unconnected-(MCU-VBUS-Pad3)") (class "Default")
      (node (ref "MCU") (pin "3") (pinfunction "VBUS_3") (pintype "passive"))
    )
  )
)
